# termoDaQ.net
KiCad netlist of a schematic drawn in EAGLE
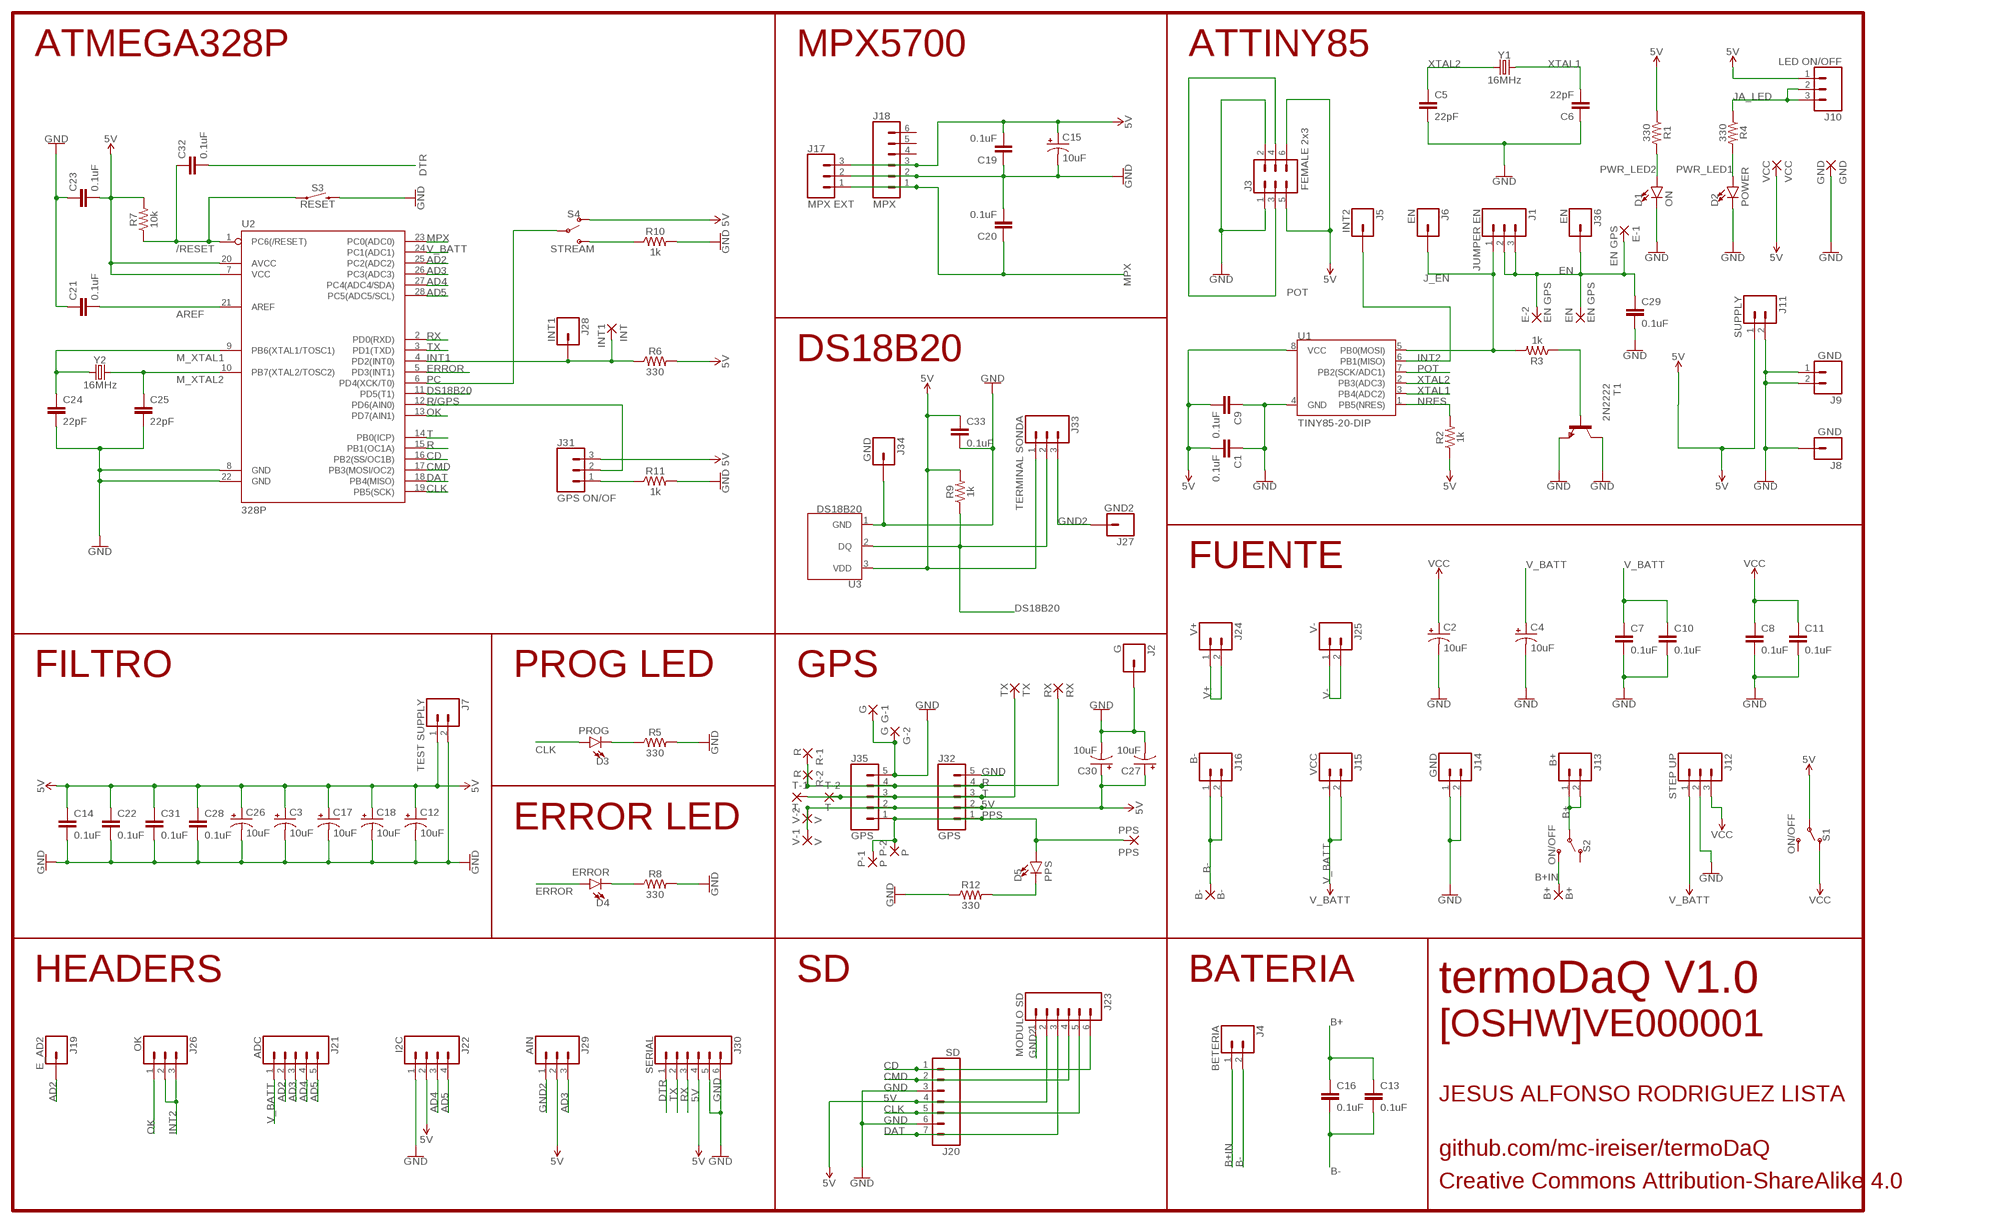
[diagram p0: schematic, sheet 1]

(export (version "E")
  (design (tool "Eeschema 10.0.6"))
  (components
    (comp (ref "B+")
      (value "B+")
      (footprint "eagle-import:SMD2,54-5,08")
      (libsource (lib "eagle-import") (part "SMD5"))
    )
    (comp (ref "B-")
      (value "B-")
      (footprint "eagle-import:SMD2,54-5,08")
      (libsource (lib "eagle-import") (part "SMD5"))
    )
    (comp (ref "C1")
      (value "0.1uF")
      (footprint "eagle-import:CAP-PTH-SMALL-KIT")
      (libsource (lib "eagle-import") (part "0.1UF-KIT-EZ-50V-20%"))
    )
    (comp (ref "C2")
      (value "10uF")
      (footprint "eagle-import:CPOL-RADIAL-2.5MM-5MM")
      (libsource (lib "eagle-import") (part "10UF-POLAR-RADIAL-2.5MM-25V-20%"))
    )
    (comp (ref "C3")
      (value "10uF")
      (footprint "eagle-import:CPOL-RADIAL-2.5MM-5MM")
      (libsource (lib "eagle-import") (part "10UF-POLAR-RADIAL-2.5MM-25V-20%"))
    )
    (comp (ref "C4")
      (value "10uF")
      (footprint "eagle-import:CPOL-RADIAL-2.5MM-5MM")
      (libsource (lib "eagle-import") (part "10UF-POLAR-RADIAL-2.5MM-25V-20%"))
    )
    (comp (ref "C5")
      (value "22pF")
      (footprint "eagle-import:CAP-PTH-2.54")
      (libsource (lib "eagle-import") (part "22PF-PTH-2.54MM-200V-5%"))
    )
    (comp (ref "C6")
      (value "22pF")
      (footprint "eagle-import:CAP-PTH-2.54")
      (libsource (lib "eagle-import") (part "22PF-PTH-2.54MM-200V-5%"))
    )
    (comp (ref "C7")
      (value "0.1uF")
      (footprint "eagle-import:CAP-PTH-SMALL-KIT")
      (libsource (lib "eagle-import") (part "0.1UF-KIT-EZ-50V-20%"))
    )
    (comp (ref "C8")
      (value "0.1uF")
      (footprint "eagle-import:CAP-PTH-SMALL-KIT")
      (libsource (lib "eagle-import") (part "0.1UF-KIT-EZ-50V-20%"))
    )
    (comp (ref "C9")
      (value "0.1uF")
      (footprint "eagle-import:CAP-PTH-SMALL-KIT")
      (libsource (lib "eagle-import") (part "0.1UF-KIT-EZ-50V-20%"))
    )
    (comp (ref "C10")
      (value "0.1uF")
      (footprint "eagle-import:CAP-PTH-SMALL-KIT")
      (libsource (lib "eagle-import") (part "0.1UF-KIT-EZ-50V-20%"))
    )
    (comp (ref "C11")
      (value "0.1uF")
      (footprint "eagle-import:CAP-PTH-SMALL-KIT")
      (libsource (lib "eagle-import") (part "0.1UF-KIT-EZ-50V-20%"))
    )
    (comp (ref "C12")
      (value "10uF")
      (footprint "eagle-import:CPOL-RADIAL-2.5MM-5MM")
      (libsource (lib "eagle-import") (part "10UF-POLAR-RADIAL-2.5MM-25V-20%"))
    )
    (comp (ref "C13")
      (value "0.1uF")
      (footprint "eagle-import:CAP-PTH-SMALL-KIT")
      (libsource (lib "eagle-import") (part "0.1UF-KIT-EZ-50V-20%"))
    )
    (comp (ref "C14")
      (value "0.1uF")
      (footprint "eagle-import:CAP-PTH-SMALL-KIT")
      (libsource (lib "eagle-import") (part "0.1UF-KIT-EZ-50V-20%"))
    )
    (comp (ref "C15")
      (value "10uF")
      (footprint "eagle-import:CPOL-RADIAL-2.5MM-5MM")
      (libsource (lib "eagle-import") (part "10UF-POLAR-RADIAL-2.5MM-25V-20%"))
    )
    (comp (ref "C16")
      (value "0.1uF")
      (footprint "eagle-import:CAP-PTH-SMALL-KIT")
      (libsource (lib "eagle-import") (part "0.1UF-KIT-EZ-50V-20%"))
    )
    (comp (ref "C17")
      (value "10uF")
      (footprint "eagle-import:CPOL-RADIAL-2.5MM-5MM")
      (libsource (lib "eagle-import") (part "10UF-POLAR-RADIAL-2.5MM-25V-20%"))
    )
    (comp (ref "C18")
      (value "10uF")
      (footprint "eagle-import:CPOL-RADIAL-2.5MM-5MM")
      (libsource (lib "eagle-import") (part "10UF-POLAR-RADIAL-2.5MM-25V-20%"))
    )
    (comp (ref "C19")
      (value "0.1uF")
      (footprint "eagle-import:CAP-PTH-SMALL-KIT")
      (libsource (lib "eagle-import") (part "0.1UF-KIT-EZ-50V-20%"))
    )
    (comp (ref "C20")
      (value "0.1uF")
      (footprint "eagle-import:CAP-PTH-SMALL-KIT")
      (libsource (lib "eagle-import") (part "0.1UF-KIT-EZ-50V-20%"))
    )
    (comp (ref "C21")
      (value "0.1uF")
      (footprint "eagle-import:CAP-PTH-SMALL-KIT")
      (libsource (lib "eagle-import") (part "0.1UF-KIT-EZ-50V-20%"))
    )
    (comp (ref "C22")
      (value "0.1uF")
      (footprint "eagle-import:CAP-PTH-SMALL-KIT")
      (libsource (lib "eagle-import") (part "0.1UF-KIT-EZ-50V-20%"))
    )
    (comp (ref "C23")
      (value "0.1uF")
      (footprint "eagle-import:CAP-PTH-SMALL-KIT")
      (libsource (lib "eagle-import") (part "0.1UF-KIT-EZ-50V-20%"))
    )
    (comp (ref "C24")
      (value "22pF")
      (footprint "eagle-import:CAP-PTH-2.54")
      (libsource (lib "eagle-import") (part "22PF-PTH-2.54MM-200V-5%"))
    )
    (comp (ref "C25")
      (value "22pF")
      (footprint "eagle-import:CAP-PTH-2.54")
      (libsource (lib "eagle-import") (part "22PF-PTH-2.54MM-200V-5%"))
    )
    (comp (ref "C26")
      (value "10uF")
      (footprint "eagle-import:CPOL-RADIAL-2.5MM-5MM")
      (libsource (lib "eagle-import") (part "10UF-POLAR-RADIAL-2.5MM-25V-20%"))
    )
    (comp (ref "C27")
      (value "10uF")
      (footprint "eagle-import:CPOL-RADIAL-2.5MM-5MM")
      (libsource (lib "eagle-import") (part "10UF-POLAR-RADIAL-2.5MM-25V-20%"))
    )
    (comp (ref "C28")
      (value "0.1uF")
      (footprint "eagle-import:CAP-PTH-SMALL-KIT")
      (libsource (lib "eagle-import") (part "0.1UF-KIT-EZ-50V-20%"))
    )
    (comp (ref "C29")
      (value "0.1uF")
      (footprint "eagle-import:CAP-PTH-SMALL-KIT")
      (libsource (lib "eagle-import") (part "0.1UF-KIT-EZ-50V-20%"))
    )
    (comp (ref "C30")
      (value "10uF")
      (footprint "eagle-import:CPOL-RADIAL-2.5MM-5MM")
      (libsource (lib "eagle-import") (part "10UF-POLAR-RADIAL-2.5MM-25V-20%"))
    )
    (comp (ref "C31")
      (value "0.1uF")
      (footprint "eagle-import:CAP-PTH-SMALL-KIT")
      (libsource (lib "eagle-import") (part "0.1UF-KIT-EZ-50V-20%"))
    )
    (comp (ref "C32")
      (value "0.1uF")
      (footprint "eagle-import:CAP-PTH-SMALL-KIT")
      (libsource (lib "eagle-import") (part "0.1UF-KIT-EZ-50V-20%"))
    )
    (comp (ref "C33")
      (value "0.1uF")
      (footprint "eagle-import:CAP-PTH-SMALL-KIT")
      (libsource (lib "eagle-import") (part "0.1UF-KIT-EZ-50V-20%"))
    )
    (comp (ref "D1")
      (value "ON")
      (footprint "eagle-import:LED_5MM")
      (libsource (lib "eagle-import") (part "LED5MM"))
    )
    (comp (ref "D2")
      (value "POWER")
      (footprint "eagle-import:LED_3MM")
      (libsource (lib "eagle-import") (part "LED3MM"))
    )
    (comp (ref "D3")
      (value "PROG")
      (footprint "eagle-import:LED_5MM")
      (libsource (lib "eagle-import") (part "LED5MM"))
    )
    (comp (ref "D4")
      (value "ERROR")
      (footprint "eagle-import:LED_5MM")
      (libsource (lib "eagle-import") (part "LED5MM"))
    )
    (comp (ref "D5")
      (value "PPS")
      (footprint "eagle-import:LED_5MM")
      (libsource (lib "eagle-import") (part "LED5MM"))
    )
    (comp (ref "E-1")
      (value "EN GPS")
      (footprint "eagle-import:SMD1,27-2,54")
      (libsource (lib "eagle-import") (part "SMD2"))
    )
    (comp (ref "E-2")
      (value "EN GPS")
      (footprint "eagle-import:SMD1,27-2,54")
      (libsource (lib "eagle-import") (part "SMD2"))
    )
    (comp (ref "EN")
      (value "EN GPS")
      (footprint "eagle-import:SMD1,27-2,54")
      (libsource (lib "eagle-import") (part "SMD2"))
    )
    (comp (ref "G-1")
      (value "G")
      (footprint "eagle-import:SMD1,27-2,54")
      (libsource (lib "eagle-import") (part "SMD2"))
    )
    (comp (ref "G-2")
      (value "G")
      (footprint "eagle-import:SMD1,27-2,54")
      (libsource (lib "eagle-import") (part "SMD2"))
    )
    (comp (ref "GND")
      (value "GND")
      (footprint "eagle-import:SMD1,27-2,54")
      (libsource (lib "eagle-import") (part "SMD2"))
    )
    (comp (ref "INT")
      (value "INT1")
      (footprint "eagle-import:SMD1,27-2,54")
      (libsource (lib "eagle-import") (part "SMD2"))
    )
    (comp (ref "J1")
      (value "JUMPER EN")
      (footprint "eagle-import:1X03")
      (libsource (lib "eagle-import") (part "CONN_03"))
    )
    (comp (ref "J2")
      (value "G")
      (footprint "eagle-import:1X01")
      (libsource (lib "eagle-import") (part "CONN_01"))
    )
    (comp (ref "J3")
      (value "FEMALE 2x3")
      (footprint "eagle-import:2X3")
      (libsource (lib "eagle-import") (part "CONN_03X2FEMALE"))
    )
    (comp (ref "J4")
      (value "BETERIA")
      (footprint "eagle-import:1X02")
      (libsource (lib "eagle-import") (part "CONN_02"))
    )
    (comp (ref "J5")
      (value "INT2")
      (footprint "eagle-import:1X01")
      (libsource (lib "eagle-import") (part "CONN_01"))
    )
    (comp (ref "J6")
      (value "EN")
      (footprint "eagle-import:1X01")
      (libsource (lib "eagle-import") (part "CONN_01"))
    )
    (comp (ref "J7")
      (value "TEST SUPPLY")
      (footprint "eagle-import:1X02")
      (libsource (lib "eagle-import") (part "CONN_02"))
    )
    (comp (ref "J8")
      (value "GND")
      (footprint "eagle-import:1X01")
      (libsource (lib "eagle-import") (part "CONN_01"))
    )
    (comp (ref "J9")
      (value "GND")
      (footprint "eagle-import:1X02")
      (libsource (lib "eagle-import") (part "CONN_02"))
    )
    (comp (ref "J10")
      (value "LED ON/OFF")
      (footprint "eagle-import:1X03")
      (libsource (lib "eagle-import") (part "CONN_03"))
    )
    (comp (ref "J11")
      (value "SUPPLY")
      (footprint "eagle-import:1X02")
      (libsource (lib "eagle-import") (part "CONN_02"))
    )
    (comp (ref "J12")
      (value "STEP UP")
      (footprint "eagle-import:1X03")
      (libsource (lib "eagle-import") (part "CONN_03"))
    )
    (comp (ref "J13")
      (value "B+")
      (footprint "eagle-import:1X02")
      (libsource (lib "eagle-import") (part "CONN_02"))
    )
    (comp (ref "J14")
      (value "GND")
      (footprint "eagle-import:1X02")
      (libsource (lib "eagle-import") (part "CONN_02"))
    )
    (comp (ref "J15")
      (value "VCC")
      (footprint "eagle-import:1X02")
      (libsource (lib "eagle-import") (part "CONN_02"))
    )
    (comp (ref "J16")
      (value "B-")
      (footprint "eagle-import:1X02")
      (libsource (lib "eagle-import") (part "CONN_02"))
    )
    (comp (ref "J17")
      (value "MPX EXT")
      (footprint "eagle-import:1X03")
      (libsource (lib "eagle-import") (part "CONN_03"))
    )
    (comp (ref "J18")
      (value "MPX")
      (footprint "eagle-import:1X06")
      (libsource (lib "eagle-import") (part "CONN_06SILK_FEMALE_PTH"))
    )
    (comp (ref "J19")
      (value "E_AD2")
      (footprint "eagle-import:1X01")
      (libsource (lib "eagle-import") (part "CONN_01"))
    )
    (comp (ref "J20")
      (value "SD")
      (footprint "eagle-import:1X07")
      (libsource (lib "eagle-import") (part "CONN_07"))
    )
    (comp (ref "J21")
      (value "ADC")
      (footprint "eagle-import:1X05")
      (libsource (lib "eagle-import") (part "CONN_05"))
    )
    (comp (ref "J22")
      (value "I2C")
      (footprint "eagle-import:1X04")
      (libsource (lib "eagle-import") (part "CONN_04"))
    )
    (comp (ref "J23")
      (value "MODULO SD")
      (footprint "eagle-import:MOLEX-1X6")
      (libsource (lib "eagle-import") (part "CONN_06POLAR"))
    )
    (comp (ref "J24")
      (value "V+")
      (footprint "eagle-import:1X02")
      (libsource (lib "eagle-import") (part "CONN_02"))
    )
    (comp (ref "J25")
      (value "V-")
      (footprint "eagle-import:1X02")
      (libsource (lib "eagle-import") (part "CONN_02"))
    )
    (comp (ref "J26")
      (value "OK")
      (footprint "eagle-import:1X03")
      (libsource (lib "eagle-import") (part "CONN_03"))
    )
    (comp (ref "J27")
      (value "GND2")
      (footprint "eagle-import:1X01")
      (libsource (lib "eagle-import") (part "CONN_01"))
    )
    (comp (ref "J28")
      (value "INT1")
      (footprint "eagle-import:1X01")
      (libsource (lib "eagle-import") (part "CONN_01"))
    )
    (comp (ref "J29")
      (value "AIN")
      (footprint "eagle-import:1X03")
      (libsource (lib "eagle-import") (part "CONN_03"))
    )
    (comp (ref "J30")
      (value "SERIAL")
      (footprint "eagle-import:1X06")
      (libsource (lib "eagle-import") (part "CONN_06SILK_FEMALE_PTH"))
    )
    (comp (ref "J31")
      (value "GPS ON/OF")
      (footprint "eagle-import:1X03")
      (libsource (lib "eagle-import") (part "CONN_03"))
    )
    (comp (ref "J32")
      (value "GPS")
      (footprint "eagle-import:1X05")
      (libsource (lib "eagle-import") (part "CONN_05"))
    )
    (comp (ref "J33")
      (value "TERMINAL SONDA")
      (footprint "eagle-import:SCREWTERMINAL-5MM-3")
      (libsource (lib "eagle-import") (part "CONN_03-SCREW-5MM"))
    )
    (comp (ref "J34")
      (value "GND")
      (footprint "eagle-import:1X01")
      (libsource (lib "eagle-import") (part "CONN_01"))
    )
    (comp (ref "J35")
      (value "GPS")
      (footprint "eagle-import:1X05")
      (libsource (lib "eagle-import") (part "CONN_05"))
    )
    (comp (ref "J36")
      (value "EN")
      (footprint "eagle-import:1X01")
      (libsource (lib "eagle-import") (part "CONN_01"))
    )
    (comp (ref "P-1")
      (value "P")
      (footprint "eagle-import:SMD1,27-2,54")
      (libsource (lib "eagle-import") (part "SMD2"))
    )
    (comp (ref "P-2")
      (value "P")
      (footprint "eagle-import:SMD1,27-2,54")
      (libsource (lib "eagle-import") (part "SMD2"))
    )
    (comp (ref "PPS")
      (value "PPS")
      (footprint "eagle-import:SMD1,27-2,54")
      (libsource (lib "eagle-import") (part "SMD2"))
    )
    (comp (ref "R-1")
      (value "R")
      (footprint "eagle-import:SMD1,27-2,54")
      (libsource (lib "eagle-import") (part "SMD2"))
    )
    (comp (ref "R-2")
      (value "R")
      (footprint "eagle-import:SMD1,27-2,54")
      (libsource (lib "eagle-import") (part "SMD2"))
    )
    (comp (ref "R1")
      (value "330")
      (footprint "eagle-import:AXIAL-0.3")
      (libsource (lib "eagle-import") (part "330OHM-HORIZ-1/10W-5%"))
    )
    (comp (ref "R2")
      (value "1k")
      (footprint "eagle-import:AXIAL-0.3")
      (libsource (lib "eagle-import") (part "1KOHM-HORIZ-1/4W-1%"))
    )
    (comp (ref "R3")
      (value "1k")
      (footprint "eagle-import:AXIAL-0.3")
      (libsource (lib "eagle-import") (part "1KOHM-HORIZ-1/4W-1%"))
    )
    (comp (ref "R4")
      (value "330")
      (footprint "eagle-import:AXIAL-0.3")
      (libsource (lib "eagle-import") (part "330OHM-HORIZ-1/10W-5%"))
    )
    (comp (ref "R5")
      (value "330")
      (footprint "eagle-import:AXIAL-0.3")
      (libsource (lib "eagle-import") (part "330OHM-HORIZ-1/10W-5%"))
    )
    (comp (ref "R6")
      (value "330")
      (footprint "eagle-import:AXIAL-0.3")
      (libsource (lib "eagle-import") (part "330OHM-HORIZ-1/10W-5%"))
    )
    (comp (ref "R7")
      (value "10k")
      (footprint "eagle-import:AXIAL-0.3")
      (libsource (lib "eagle-import") (part "10KOHM-HORIZ-1/4W-5%"))
    )
    (comp (ref "R8")
      (value "330")
      (footprint "eagle-import:AXIAL-0.3")
      (libsource (lib "eagle-import") (part "330OHM-HORIZ-1/10W-5%"))
    )
    (comp (ref "R9")
      (value "1k")
      (footprint "eagle-import:AXIAL-0.3")
      (libsource (lib "eagle-import") (part "1KOHM-HORIZ-1/4W-1%"))
    )
    (comp (ref "R10")
      (value "1k")
      (footprint "eagle-import:AXIAL-0.3")
      (fields (field (name "SPICEPREFIX") "R"))
      (libsource (lib "eagle-import") (part "1KOHM-HORIZ-1/4W-1%"))
    )
    (comp (ref "R11")
      (value "1k")
      (footprint "eagle-import:AXIAL-0.3")
      (libsource (lib "eagle-import") (part "1KOHM-HORIZ-1/4W-1%"))
    )
    (comp (ref "R12")
      (value "330")
      (footprint "eagle-import:AXIAL-0.3")
      (libsource (lib "eagle-import") (part "330OHM-HORIZ-1/10W-5%"))
    )
    (comp (ref "RX")
      (value "RX")
      (footprint "eagle-import:SMD1,27-2,54")
      (libsource (lib "eagle-import") (part "SMD2"))
    )
    (comp (ref "S1")
      (value "ON/OFF")
      (footprint "eagle-import:SWITCH_SPDT_PTH_11.6X4.0MM")
      (libsource (lib "eagle-import") (part "SWITCH-SPDT-PTH-11.6X4.0MM"))
    )
    (comp (ref "S2")
      (value "ON/OFF")
      (footprint "eagle-import:SWITCH_SPDT_PTH_11.6X4.0MM")
      (libsource (lib "eagle-import") (part "SWITCH-SPDT-PTH-11.6X4.0MM"))
    )
    (comp (ref "S3")
      (value "RESET")
      (footprint "eagle-import:TACTILE_SWITCH_PTH_6.0MM")
      (libsource (lib "eagle-import") (part "MOMENTARY-SWITCH-SPST-PTH-6.0MM"))
    )
    (comp (ref "S4")
      (value "STREAM")
      (footprint "eagle-import:SWITCH_SPDT_PTH_11.6X4.0MM")
      (fields (field (name "SPICEPREFIX") "J"))
      (libsource (lib "eagle-import") (part "SWITCH-SPDT-PTH-11.6X4.0MM"))
    )
    (comp (ref "T-1")
      (value "T")
      (footprint "eagle-import:SMD1,27-2,54")
      (libsource (lib "eagle-import") (part "SMD2"))
    )
    (comp (ref "T-2")
      (value "T")
      (footprint "eagle-import:SMD1,27-2,54")
      (libsource (lib "eagle-import") (part "SMD2"))
    )
    (comp (ref "T1")
      (value "2N2222")
      (footprint "eagle-import:TO92-EBC-OVAL")
      (libsource (lib "eagle-import") (part "2N2222"))
    )
    (comp (ref "TX")
      (value "TX")
      (footprint "eagle-import:SMD1,27-2,54")
      (libsource (lib "eagle-import") (part "SMD2"))
    )
    (comp (ref "U1")
      (value "TINY85-20-DIP")
      (footprint "eagle-import:DIP08_MCU")
      (libsource (lib "eagle-import") (part "ATTINY45TINY85-20-DIP"))
    )
    (comp (ref "U2")
      (value "328P")
      (footprint "eagle-import:DIP28")
      (libsource (lib "eagle-import") (part "ATMEGA328P_PDIP"))
    )
    (comp (ref "U3")
      (value "DS18B20")
      (footprint "eagle-import:TO-92-AMMO")
      (libsource (lib "eagle-import") (part "DS18B20"))
    )
    (comp (ref "V-1")
      (value "V")
      (footprint "eagle-import:SMD1,27-2,54")
      (libsource (lib "eagle-import") (part "SMD2"))
    )
    (comp (ref "V-2")
      (value "V")
      (footprint "eagle-import:SMD1,27-2,54")
      (libsource (lib "eagle-import") (part "SMD2"))
    )
    (comp (ref "VCC")
      (value "VCC")
      (footprint "eagle-import:SMD1,27-2,54")
      (libsource (lib "eagle-import") (part "SMD2"))
    )
    (comp (ref "Y1")
      (value "16MHz")
      (footprint "eagle-import:HC49US")
      (libsource (lib "eagle-import") (part "CRYSTAL-16MHZPTH-HC49US"))
    )
    (comp (ref "Y2")
      (value "16MHz")
      (footprint "eagle-import:HC49US")
      (libsource (lib "eagle-import") (part "CRYSTAL-16MHZPTH-HC49US"))
    )
  )
  (nets
    (net (code "1") (name "/AD2") (class "Default")
      (node (ref "J19") (pin "1") (pinfunction "1_1") (pintype "passive"))
      (node (ref "J21") (pin "2") (pinfunction "2_2") (pintype "passive"))
      (node (ref "U2") (pin "25") (pinfunction "PC2(ADC2)_25") (pintype "bidirectional"))
    )
    (net (code "2") (name "/AD3") (class "Default")
      (node (ref "J21") (pin "3") (pinfunction "3_3") (pintype "passive"))
      (node (ref "J29") (pin "3") (pinfunction "3_3") (pintype "passive"))
      (node (ref "U2") (pin "26") (pinfunction "PC3(ADC3)_26") (pintype "bidirectional"))
    )
    (net (code "3") (name "/AD4") (class "Default")
      (node (ref "J21") (pin "4") (pinfunction "4_4") (pintype "passive"))
      (node (ref "J22") (pin "3") (pinfunction "3_3") (pintype "passive"))
      (node (ref "U2") (pin "27") (pinfunction "PC4(ADC4/SDA)_27") (pintype "bidirectional"))
    )
    (net (code "4") (name "/AD5") (class "Default")
      (node (ref "J21") (pin "5") (pinfunction "5_5") (pintype "passive"))
      (node (ref "J22") (pin "4") (pinfunction "4_4") (pintype "passive"))
      (node (ref "U2") (pin "28") (pinfunction "PC5(ADC5/SCL)_28") (pintype "bidirectional"))
    )
    (net (code "5") (name "/AREF") (class "Default")
      (node (ref "C21") (pin "2") (pinfunction "2_2") (pintype "passive"))
      (node (ref "U2") (pin "21") (pinfunction "AREF_21") (pintype "bidirectional"))
    )
    (net (code "6") (name "/B+") (class "Default")
      (node (ref "C13") (pin "1") (pinfunction "1_1") (pintype "passive"))
      (node (ref "C16") (pin "1") (pinfunction "1_1") (pintype "passive"))
      (node (ref "J13") (pin "1") (pinfunction "1_1") (pintype "passive"))
      (node (ref "J13") (pin "2") (pinfunction "2_2") (pintype "passive"))
      (node (ref "S2") (pin "2") (pinfunction "P_2") (pintype "passive"))
    )
    (net (code "7") (name "/B+IN") (class "Default")
      (node (ref "B+") (pin "1") (pinfunction "P_1") (pintype "passive"))
      (node (ref "J4") (pin "1") (pinfunction "1_1") (pintype "passive"))
      (node (ref "S2") (pin "3") (pinfunction "S_3") (pintype "passive"))
    )
    (net (code "8") (name "/B-") (class "Default")
      (node (ref "B-") (pin "1") (pinfunction "P_1") (pintype "passive"))
      (node (ref "C13") (pin "2") (pinfunction "2_2") (pintype "passive"))
      (node (ref "C16") (pin "2") (pinfunction "2_2") (pintype "passive"))
      (node (ref "J16") (pin "1") (pinfunction "1_1") (pintype "passive"))
      (node (ref "J16") (pin "2") (pinfunction "2_2") (pintype "passive"))
      (node (ref "J4") (pin "2") (pinfunction "2_2") (pintype "passive"))
    )
    (net (code "9") (name "/CD") (class "Default")
      (node (ref "J20") (pin "1") (pinfunction "1_1") (pintype "passive"))
      (node (ref "J23") (pin "6") (pinfunction "6_6") (pintype "passive"))
      (node (ref "U2") (pin "16") (pinfunction "PB2(SS/OC1B)_16") (pintype "bidirectional"))
    )
    (net (code "10") (name "/CLK") (class "Default")
      (node (ref "D3") (pin "A") (pinfunction "A_A") (pintype "passive"))
      (node (ref "J20") (pin "5") (pinfunction "5_5") (pintype "passive"))
      (node (ref "J23") (pin "5") (pinfunction "5_5") (pintype "passive"))
      (node (ref "U2") (pin "19") (pinfunction "PB5(SCK)_19") (pintype "bidirectional"))
    )
    (net (code "11") (name "/CMD") (class "Default")
      (node (ref "J20") (pin "2") (pinfunction "2_2") (pintype "passive"))
      (node (ref "J23") (pin "4") (pinfunction "4_4") (pintype "passive"))
      (node (ref "U2") (pin "17") (pinfunction "PB3(MOSI/OC2)_17") (pintype "bidirectional"))
    )
    (net (code "12") (name "/DAT") (class "Default")
      (node (ref "J20") (pin "7") (pinfunction "7_7") (pintype "passive"))
      (node (ref "J23") (pin "3") (pinfunction "3_3") (pintype "passive"))
      (node (ref "U2") (pin "18") (pinfunction "PB4(MISO)_18") (pintype "bidirectional"))
    )
    (net (code "13") (name "/DS18B20") (class "Default")
      (node (ref "J33") (pin "2") (pinfunction "2_2") (pintype "passive"))
      (node (ref "R9") (pin "P$1") (pinfunction "1_P$1") (pintype "passive"))
      (node (ref "U2") (pin "11") (pinfunction "PD5(T1)_11") (pintype "bidirectional"))
      (node (ref "U3") (pin "2") (pinfunction "DQ_2") (pintype "bidirectional"))
    )
    (net (code "14") (name "/DTR") (class "Default")
      (node (ref "C32") (pin "2") (pinfunction "2_2") (pintype "passive"))
      (node (ref "J30") (pin "1") (pinfunction "1_1") (pintype "passive"))
    )
    (net (code "15") (name "/EN") (class "Default")
      (node (ref "C29") (pin "1") (pinfunction "1_1") (pintype "passive"))
      (node (ref "E-1") (pin "1") (pinfunction "P_1") (pintype "passive"))
      (node (ref "E-2") (pin "1") (pinfunction "P_1") (pintype "passive"))
      (node (ref "EN") (pin "1") (pinfunction "P_1") (pintype "passive"))
      (node (ref "J1") (pin "2") (pinfunction "2_2") (pintype "passive"))
      (node (ref "J1") (pin "3") (pinfunction "3_3") (pintype "passive"))
      (node (ref "J36") (pin "1") (pinfunction "1_1") (pintype "passive"))
    )
    (net (code "16") (name "/ERROR") (class "Default")
      (node (ref "D4") (pin "A") (pinfunction "A_A") (pintype "passive"))
      (node (ref "U2") (pin "5") (pinfunction "PD3(INT1)_5") (pintype "bidirectional"))
    )
    (net (code "17") (name "/GND2") (class "Default")
      (node (ref "J23") (pin "1") (pinfunction "1_1") (pintype "passive"))
      (node (ref "J27") (pin "1") (pinfunction "1_1") (pintype "passive"))
      (node (ref "J29") (pin "1") (pinfunction "1_1") (pintype "passive"))
      (node (ref "J33") (pin "3") (pinfunction "3_3") (pintype "passive"))
    )
    (net (code "18") (name "/INT1") (class "Default")
      (node (ref "INT") (pin "1") (pinfunction "P_1") (pintype "passive"))
      (node (ref "J28") (pin "1") (pinfunction "1_1") (pintype "passive"))
      (node (ref "R6") (pin "P$1") (pinfunction "1_P$1") (pintype "passive"))
      (node (ref "U2") (pin "4") (pinfunction "PD2(INT0)_4") (pintype "bidirectional"))
    )
    (net (code "19") (name "/INT2") (class "Default")
      (node (ref "J26") (pin "2") (pinfunction "2_2") (pintype "passive"))
      (node (ref "J26") (pin "3") (pinfunction "3_3") (pintype "passive"))
      (node (ref "J5") (pin "1") (pinfunction "1_1") (pintype "passive"))
      (node (ref "U1") (pin "6") (pinfunction "PB1(MISO)_6") (pintype "bidirectional"))
    )
    (net (code "20") (name "/JA_LED") (class "Default")
      (node (ref "J10") (pin "2") (pinfunction "2_2") (pintype "passive"))
      (node (ref "J10") (pin "3") (pinfunction "3_3") (pintype "passive"))
      (node (ref "R4") (pin "P$1") (pinfunction "1_P$1") (pintype "passive"))
    )
    (net (code "21") (name "/J_EN") (class "Default")
      (node (ref "J1") (pin "1") (pinfunction "1_1") (pintype "passive"))
      (node (ref "J6") (pin "1") (pinfunction "1_1") (pintype "passive"))
      (node (ref "R3") (pin "P$2") (pinfunction "2_P$2") (pintype "passive"))
      (node (ref "U1") (pin "5") (pinfunction "PB0(MOSI)_5") (pintype "bidirectional"))
    )
    (net (code "22") (name "/MPX") (class "Default")
      (node (ref "C20") (pin "1") (pinfunction "1_1") (pintype "passive"))
      (node (ref "J17") (pin "1") (pinfunction "1_1") (pintype "passive"))
      (node (ref "J18") (pin "1") (pinfunction "1_1") (pintype "passive"))
      (node (ref "U2") (pin "23") (pinfunction "PC0(ADC0)_23") (pintype "bidirectional"))
    )
    (net (code "23") (name "/M_XTAL1") (class "Default")
      (node (ref "C24") (pin "1") (pinfunction "1_1") (pintype "passive"))
      (node (ref "U2") (pin "9") (pinfunction "PB6(XTAL1/TOSC1)_9") (pintype "bidirectional"))
      (node (ref "Y2") (pin "1") (pinfunction "1_1") (pintype "passive"))
    )
    (net (code "24") (name "/M_XTAL2") (class "Default")
      (node (ref "C25") (pin "1") (pinfunction "1_1") (pintype "passive"))
      (node (ref "U2") (pin "10") (pinfunction "PB7(XTAL2/TOSC2)_10") (pintype "bidirectional"))
      (node (ref "Y2") (pin "2") (pinfunction "2_2") (pintype "passive"))
    )
    (net (code "25") (name "/NRES") (class "Default")
      (node (ref "R2") (pin "P$2") (pinfunction "2_P$2") (pintype "passive"))
      (node (ref "U1") (pin "1") (pinfunction "PB5(NRES)_1") (pintype "bidirectional"))
    )
    (net (code "26") (name "/OK") (class "Default")
      (node (ref "J26") (pin "1") (pinfunction "1_1") (pintype "passive"))
      (node (ref "U2") (pin "13") (pinfunction "PD7(AIN1)_13") (pintype "bidirectional"))
    )
    (net (code "27") (name "/PC") (class "Default")
      (node (ref "S4") (pin "2") (pinfunction "P_2") (pintype "passive"))
      (node (ref "U2") (pin "6") (pinfunction "PD4(XCK/T0)_6") (pintype "bidirectional"))
    )
    (net (code "28") (name "/POT") (class "Default")
      (node (ref "J3") (pin "3") (pinfunction "3_3") (pintype "bidirectional"))
      (node (ref "J3") (pin "4") (pinfunction "4_4") (pintype "bidirectional"))
      (node (ref "U1") (pin "7") (pinfunction "PB2(SCK/ADC1)_7") (pintype "bidirectional"))
    )
    (net (code "29") (name "/PPS") (class "Default")
      (node (ref "D5") (pin "A") (pinfunction "A_A") (pintype "passive"))
      (node (ref "J32") (pin "1") (pinfunction "1_1") (pintype "passive"))
      (node (ref "J35") (pin "1") (pinfunction "1_1") (pintype "passive"))
      (node (ref "P-1") (pin "1") (pinfunction "P_1") (pintype "passive"))
      (node (ref "P-2") (pin "1") (pinfunction "P_1") (pintype "passive"))
      (node (ref "PPS") (pin "1") (pinfunction "P_1") (pintype "passive"))
    )
    (net (code "30") (name "/PWR_LED1") (class "Default")
      (node (ref "D2") (pin "A") (pinfunction "A_A") (pintype "passive"))
      (node (ref "R4") (pin "P$2") (pinfunction "2_P$2") (pintype "passive"))
    )
    (net (code "31") (name "/PWR_LED2") (class "Default")
      (node (ref "D1") (pin "A") (pinfunction "A_A") (pintype "passive"))
      (node (ref "R1") (pin "P$2") (pinfunction "2_P$2") (pintype "passive"))
    )
    (net (code "32") (name "/R") (class "Default")
      (node (ref "J32") (pin "4") (pinfunction "4_4") (pintype "passive"))
      (node (ref "J35") (pin "4") (pinfunction "4_4") (pintype "passive"))
      (node (ref "R-1") (pin "1") (pinfunction "P_1") (pintype "passive"))
      (node (ref "R-2") (pin "1") (pinfunction "P_1") (pintype "passive"))
      (node (ref "RX") (pin "1") (pinfunction "P_1") (pintype "passive"))
      (node (ref "U2") (pin "15") (pinfunction "PB1(OC1A)_15") (pintype "bidirectional"))
    )
    (net (code "33") (name "/RX") (class "Default")
      (node (ref "J30") (pin "3") (pinfunction "3_3") (pintype "passive"))
      (node (ref "U2") (pin "2") (pinfunction "PD0(RXD)_2") (pintype "bidirectional"))
    )
    (net (code "34") (name "/R{slash}GPS") (class "Default")
      (node (ref "J31") (pin "2") (pinfunction "2_2") (pintype "passive"))
      (node (ref "U2") (pin "12") (pinfunction "PD6(AIN0)_12") (pintype "bidirectional"))
    )
    (net (code "35") (name "/T") (class "Default")
      (node (ref "J32") (pin "3") (pinfunction "3_3") (pintype "passive"))
      (node (ref "J35") (pin "3") (pinfunction "3_3") (pintype "passive"))
      (node (ref "T-1") (pin "1") (pinfunction "P_1") (pintype "passive"))
      (node (ref "T-2") (pin "1") (pinfunction "P_1") (pintype "passive"))
      (node (ref "TX") (pin "1") (pinfunction "P_1") (pintype "passive"))
      (node (ref "U2") (pin "14") (pinfunction "PB0(ICP)_14") (pintype "bidirectional"))
    )
    (net (code "36") (name "/TX") (class "Default")
      (node (ref "J30") (pin "2") (pinfunction "2_2") (pintype "passive"))
      (node (ref "U2") (pin "3") (pinfunction "PD1(TXD)_3") (pintype "bidirectional"))
    )
    (net (code "37") (name "/V+") (class "Default")
      (node (ref "J24") (pin "1") (pinfunction "1_1") (pintype "passive"))
      (node (ref "J24") (pin "2") (pinfunction "2_2") (pintype "passive"))
    )
    (net (code "38") (name "/V-") (class "Default")
      (node (ref "J25") (pin "1") (pinfunction "1_1") (pintype "passive"))
      (node (ref "J25") (pin "2") (pinfunction "2_2") (pintype "passive"))
    )
    (net (code "39") (name "/XTAL1") (class "Default")
      (node (ref "C6") (pin "2") (pinfunction "2_2") (pintype "passive"))
      (node (ref "U1") (pin "3") (pinfunction "PB4(ADC2)_3") (pintype "bidirectional"))
      (node (ref "Y1") (pin "2") (pinfunction "2_2") (pintype "passive"))
    )
    (net (code "40") (name "/XTAL2") (class "Default")
      (node (ref "C5") (pin "1") (pinfunction "1_1") (pintype "passive"))
      (node (ref "U1") (pin "2") (pinfunction "PB3(ADC3)_2") (pintype "bidirectional"))
      (node (ref "Y1") (pin "1") (pinfunction "1_1") (pintype "passive"))
    )
    (net (code "41") (name "/{slash}RESET") (class "Default")
      (node (ref "C32") (pin "1") (pinfunction "1_1") (pintype "passive"))
      (node (ref "R7") (pin "P$1") (pinfunction "1_P$1") (pintype "passive"))
      (node (ref "S3") (pin "1") (pinfunction "1_1") (pintype "passive"))
      (node (ref "U2") (pin "1") (pinfunction "PC6(/RESET)_1") (pintype "bidirectional"))
    )
    (net (code "42") (name "5V") (class "Default")
      (node (ref "C1") (pin "2") (pinfunction "2_2") (pintype "passive"))
      (node (ref "C12") (pin "1") (pinfunction "+_1") (pintype "passive"))
      (node (ref "C14") (pin "1") (pinfunction "1_1") (pintype "passive"))
      (node (ref "C15") (pin "1") (pinfunction "+_1") (pintype "passive"))
      (node (ref "C17") (pin "1") (pinfunction "+_1") (pintype "passive"))
      (node (ref "C18") (pin "1") (pinfunction "+_1") (pintype "passive"))
      (node (ref "C19") (pin "2") (pinfunction "2_2") (pintype "passive"))
      (node (ref "C22") (pin "1") (pinfunction "1_1") (pintype "passive"))
      (node (ref "C23") (pin "2") (pinfunction "2_2") (pintype "passive"))
      (node (ref "C26") (pin "1") (pinfunction "+_1") (pintype "passive"))
      (node (ref "C27") (pin "1") (pinfunction "+_1") (pintype "passive"))
      (node (ref "C28") (pin "1") (pinfunction "1_1") (pintype "passive"))
      (node (ref "C3") (pin "1") (pinfunction "+_1") (pintype "passive"))
      (node (ref "C30") (pin "1") (pinfunction "+_1") (pintype "passive"))
      (node (ref "C31") (pin "1") (pinfunction "1_1") (pintype "passive"))
      (node (ref "C33") (pin "1") (pinfunction "1_1") (pintype "passive"))
      (node (ref "C9") (pin "2") (pinfunction "2_2") (pintype "passive"))
      (node (ref "J10") (pin "1") (pinfunction "1_1") (pintype "passive"))
      (node (ref "J11") (pin "1") (pinfunction "1_1") (pintype "passive"))
      (node (ref "J17") (pin "3") (pinfunction "3_3") (pintype "passive"))
      (node (ref "J18") (pin "3") (pinfunction "3_3") (pintype "passive"))
      (node (ref "J20") (pin "4") (pinfunction "4_4") (pintype "passive"))
      (node (ref "J22") (pin "2") (pinfunction "2_2") (pintype "passive"))
      (node (ref "J23") (pin "2") (pinfunction "2_2") (pintype "passive"))
      (node (ref "J29") (pin "2") (pinfunction "2_2") (pintype "passive"))
      (node (ref "J3") (pin "5") (pinfunction "5_5") (pintype "bidirectional"))
      (node (ref "J3") (pin "6") (pinfunction "6_6") (pintype "bidirectional"))
      (node (ref "J30") (pin "4") (pinfunction "4_4") (pintype "passive"))
      (node (ref "J31") (pin "3") (pinfunction "3_3") (pintype "passive"))
      (node (ref "J32") (pin "2") (pinfunction "2_2") (pintype "passive"))
      (node (ref "J33") (pin "1") (pinfunction "1_1") (pintype "passive"))
      (node (ref "J35") (pin "2") (pinfunction "2_2") (pintype "passive"))
      (node (ref "J7") (pin "1") (pinfunction "1_1") (pintype "passive"))
      (node (ref "R1") (pin "P$1") (pinfunction "1_P$1") (pintype "passive"))
      (node (ref "R2") (pin "P$1") (pinfunction "1_P$1") (pintype "passive"))
      (node (ref "R6") (pin "P$2") (pinfunction "2_P$2") (pintype "passive"))
      (node (ref "R7") (pin "P$2") (pinfunction "2_P$2") (pintype "passive"))
      (node (ref "R9") (pin "P$2") (pinfunction "2_P$2") (pintype "passive"))
      (node (ref "S1") (pin "2") (pinfunction "P_2") (pintype "passive"))
      (node (ref "S4") (pin "1") (pinfunction "O_1") (pintype "passive"))
      (node (ref "U1") (pin "8") (pinfunction "VCC_8") (pintype "bidirectional"))
      (node (ref "U2") (pin "20") (pinfunction "AVCC_20") (pintype "bidirectional"))
      (node (ref "U2") (pin "7") (pinfunction "VCC_7") (pintype "bidirectional"))
      (node (ref "U3") (pin "3") (pinfunction "VDD_3") (pintype "power_in"))
      (node (ref "V-1") (pin "1") (pinfunction "P_1") (pintype "passive"))
      (node (ref "V-2") (pin "1") (pinfunction "P_1") (pintype "passive"))
      (node (ref "VCC") (pin "1") (pinfunction "P_1") (pintype "passive"))
    )
    (net (code "43") (name "GND") (class "Default")
      (node (ref "C1") (pin "1") (pinfunction "1_1") (pintype "passive"))
      (node (ref "C10") (pin "2") (pinfunction "2_2") (pintype "passive"))
      (node (ref "C11") (pin "2") (pinfunction "2_2") (pintype "passive"))
      (node (ref "C12") (pin "2") (pinfunction "-_2") (pintype "passive"))
      (node (ref "C14") (pin "2") (pinfunction "2_2") (pintype "passive"))
      (node (ref "C15") (pin "2") (pinfunction "-_2") (pintype "passive"))
      (node (ref "C17") (pin "2") (pinfunction "-_2") (pintype "passive"))
      (node (ref "C18") (pin "2") (pinfunction "-_2") (pintype "passive"))
      (node (ref "C19") (pin "1") (pinfunction "1_1") (pintype "passive"))
      (node (ref "C2") (pin "2") (pinfunction "-_2") (pintype "passive"))
      (node (ref "C20") (pin "2") (pinfunction "2_2") (pintype "passive"))
      (node (ref "C21") (pin "1") (pinfunction "1_1") (pintype "passive"))
      (node (ref "C22") (pin "2") (pinfunction "2_2") (pintype "passive"))
      (node (ref "C23") (pin "1") (pinfunction "1_1") (pintype "passive"))
      (node (ref "C24") (pin "2") (pinfunction "2_2") (pintype "passive"))
      (node (ref "C25") (pin "2") (pinfunction "2_2") (pintype "passive"))
      (node (ref "C26") (pin "2") (pinfunction "-_2") (pintype "passive"))
      (node (ref "C27") (pin "2") (pinfunction "-_2") (pintype "passive"))
      (node (ref "C28") (pin "2") (pinfunction "2_2") (pintype "passive"))
      (node (ref "C29") (pin "2") (pinfunction "2_2") (pintype "passive"))
      (node (ref "C3") (pin "2") (pinfunction "-_2") (pintype "passive"))
      (node (ref "C30") (pin "2") (pinfunction "-_2") (pintype "passive"))
      (node (ref "C31") (pin "2") (pinfunction "2_2") (pintype "passive"))
      (node (ref "C33") (pin "2") (pinfunction "2_2") (pintype "passive"))
      (node (ref "C4") (pin "2") (pinfunction "-_2") (pintype "passive"))
      (node (ref "C5") (pin "2") (pinfunction "2_2") (pintype "passive"))
      (node (ref "C6") (pin "1") (pinfunction "1_1") (pintype "passive"))
      (node (ref "C7") (pin "2") (pinfunction "2_2") (pintype "passive"))
      (node (ref "C8") (pin "2") (pinfunction "2_2") (pintype "passive"))
      (node (ref "C9") (pin "1") (pinfunction "1_1") (pintype "passive"))
      (node (ref "D1") (pin "K") (pinfunction "C_K") (pintype "passive"))
      (node (ref "D2") (pin "K") (pinfunction "C_K") (pintype "passive"))
      (node (ref "G-1") (pin "1") (pinfunction "P_1") (pintype "passive"))
      (node (ref "G-2") (pin "1") (pinfunction "P_1") (pintype "passive"))
      (node (ref "GND") (pin "1") (pinfunction "P_1") (pintype "passive"))
      (node (ref "J11") (pin "2") (pinfunction "2_2") (pintype "passive"))
      (node (ref "J12") (pin "2") (pinfunction "2_2") (pintype "passive"))
      (node (ref "J14") (pin "1") (pinfunction "1_1") (pintype "passive"))
      (node (ref "J14") (pin "2") (pinfunction "2_2") (pintype "passive"))
      (node (ref "J17") (pin "2") (pinfunction "2_2") (pintype "passive"))
      (node (ref "J18") (pin "2") (pinfunction "2_2") (pintype "passive"))
      (node (ref "J2") (pin "1") (pinfunction "1_1") (pintype "passive"))
      (node (ref "J20") (pin "3") (pinfunction "3_3") (pintype "passive"))
      (node (ref "J20") (pin "6") (pinfunction "6_6") (pintype "passive"))
      (node (ref "J22") (pin "1") (pinfunction "1_1") (pintype "passive"))
      (node (ref "J3") (pin "1") (pinfunction "1_1") (pintype "bidirectional"))
      (node (ref "J3") (pin "2") (pinfunction "2_2") (pintype "bidirectional"))
      (node (ref "J30") (pin "5") (pinfunction "5_5") (pintype "passive"))
      (node (ref "J30") (pin "6") (pinfunction "6_6") (pintype "passive"))
      (node (ref "J32") (pin "5") (pinfunction "5_5") (pintype "passive"))
      (node (ref "J34") (pin "1") (pinfunction "1_1") (pintype "passive"))
      (node (ref "J35") (pin "5") (pinfunction "5_5") (pintype "passive"))
      (node (ref "J7") (pin "2") (pinfunction "2_2") (pintype "passive"))
      (node (ref "J8") (pin "1") (pinfunction "1_1") (pintype "passive"))
      (node (ref "J9") (pin "1") (pinfunction "1_1") (pintype "passive"))
      (node (ref "J9") (pin "2") (pinfunction "2_2") (pintype "passive"))
      (node (ref "R10") (pin "P$2") (pinfunction "2_P$2") (pintype "passive"))
      (node (ref "R11") (pin "P$2") (pinfunction "2_P$2") (pintype "passive"))
      (node (ref "R12") (pin "P$1") (pinfunction "1_P$1") (pintype "passive"))
      (node (ref "R5") (pin "P$2") (pinfunction "2_P$2") (pintype "passive"))
      (node (ref "R8") (pin "P$2") (pinfunction "2_P$2") (pintype "passive"))
      (node (ref "S3") (pin "3") (pinfunction "2_3") (pintype "passive"))
      (node (ref "T1") (pin "C") (pinfunction "C_C") (pintype "passive"))
      (node (ref "T1") (pin "E") (pinfunction "E_E") (pintype "passive"))
      (node (ref "U1") (pin "4") (pinfunction "GND_4") (pintype "bidirectional"))
      (node (ref "U2") (pin "22") (pinfunction "GND_22") (pintype "bidirectional"))
      (node (ref "U2") (pin "8") (pinfunction "GND_8") (pintype "bidirectional"))
      (node (ref "U3") (pin "1") (pinfunction "GND_1") (pintype "power_in"))
    )
    (net (code "44") (name "Net-(D3-C)") (class "Default")
      (node (ref "D3") (pin "K") (pinfunction "C_K") (pintype "passive"))
      (node (ref "R5") (pin "P$1") (pinfunction "1_P$1") (pintype "passive"))
    )
    (net (code "45") (name "Net-(D4-C)") (class "Default")
      (node (ref "D4") (pin "K") (pinfunction "C_K") (pintype "passive"))
      (node (ref "R8") (pin "P$1") (pinfunction "1_P$1") (pintype "passive"))
    )
    (net (code "46") (name "Net-(D5-C)") (class "Default")
      (node (ref "D5") (pin "K") (pinfunction "C_K") (pintype "passive"))
      (node (ref "R12") (pin "P$2") (pinfunction "2_P$2") (pintype "passive"))
    )
    (net (code "47") (name "Net-(R3-1)") (class "Default")
      (node (ref "R3") (pin "P$1") (pinfunction "1_P$1") (pintype "passive"))
      (node (ref "T1") (pin "B") (pinfunction "B_B") (pintype "passive"))
    )
    (net (code "48") (name "Net-(R10-1)") (class "Default")
      (node (ref "R10") (pin "P$1") (pinfunction "1_P$1") (pintype "passive"))
      (node (ref "S4") (pin "3") (pinfunction "S_3") (pintype "passive"))
    )
    (net (code "49") (name "Net-(R11-1)") (class "Default")
      (node (ref "J31") (pin "1") (pinfunction "1_1") (pintype "passive"))
      (node (ref "R11") (pin "P$1") (pinfunction "1_P$1") (pintype "passive"))
    )
    (net (code "50") (name "VCC") (class "Default")
      (node (ref "C11") (pin "1") (pinfunction "1_1") (pintype "passive"))
      (node (ref "C2") (pin "1") (pinfunction "+_1") (pintype "passive"))
      (node (ref "C8") (pin "1") (pinfunction "1_1") (pintype "passive"))
      (node (ref "J12") (pin "3") (pinfunction "3_3") (pintype "passive"))
      (node (ref "S1") (pin "1") (pinfunction "O_1") (pintype "passive"))
    )
    (net (code "51") (name "V_BATT") (class "Default")
      (node (ref "C10") (pin "1") (pinfunction "1_1") (pintype "passive"))
      (node (ref "C4") (pin "1") (pinfunction "+_1") (pintype "passive"))
      (node (ref "C7") (pin "1") (pinfunction "1_1") (pintype "passive"))
      (node (ref "J12") (pin "1") (pinfunction "1_1") (pintype "passive"))
      (node (ref "J15") (pin "1") (pinfunction "1_1") (pintype "passive"))
      (node (ref "J15") (pin "2") (pinfunction "2_2") (pintype "passive"))
      (node (ref "J21") (pin "1") (pinfunction "1_1") (pintype "passive"))
      (node (ref "U2") (pin "24") (pinfunction "PC1(ADC1)_24") (pintype "bidirectional"))
    )
    (net (code "52") (name "unconnected-(J18-Pad4)") (class "Default")
      (node (ref "J18") (pin "4") (pinfunction "4_4") (pintype "passive"))
    )
    (net (code "53") (name "unconnected-(J18-Pad5)") (class "Default")
      (node (ref "J18") (pin "5") (pinfunction "5_5") (pintype "passive"))
    )
    (net (code "54") (name "unconnected-(J18-Pad6)") (class "Default")
      (node (ref "J18") (pin "6") (pinfunction "6_6") (pintype "passive"))
    )
    (net (code "55") (name "unconnected-(S1-S-Pad3)") (class "Default")
      (node (ref "S1") (pin "3") (pinfunction "S_3") (pintype "passive"))
    )
    (net (code "56") (name "unconnected-(S2-O-Pad1)") (class "Default")
      (node (ref "S2") (pin "1") (pinfunction "O_1") (pintype "passive"))
    )
  )
)
